# RP2040.net
KiCad netlist of a schematic drawn in Altium Designer
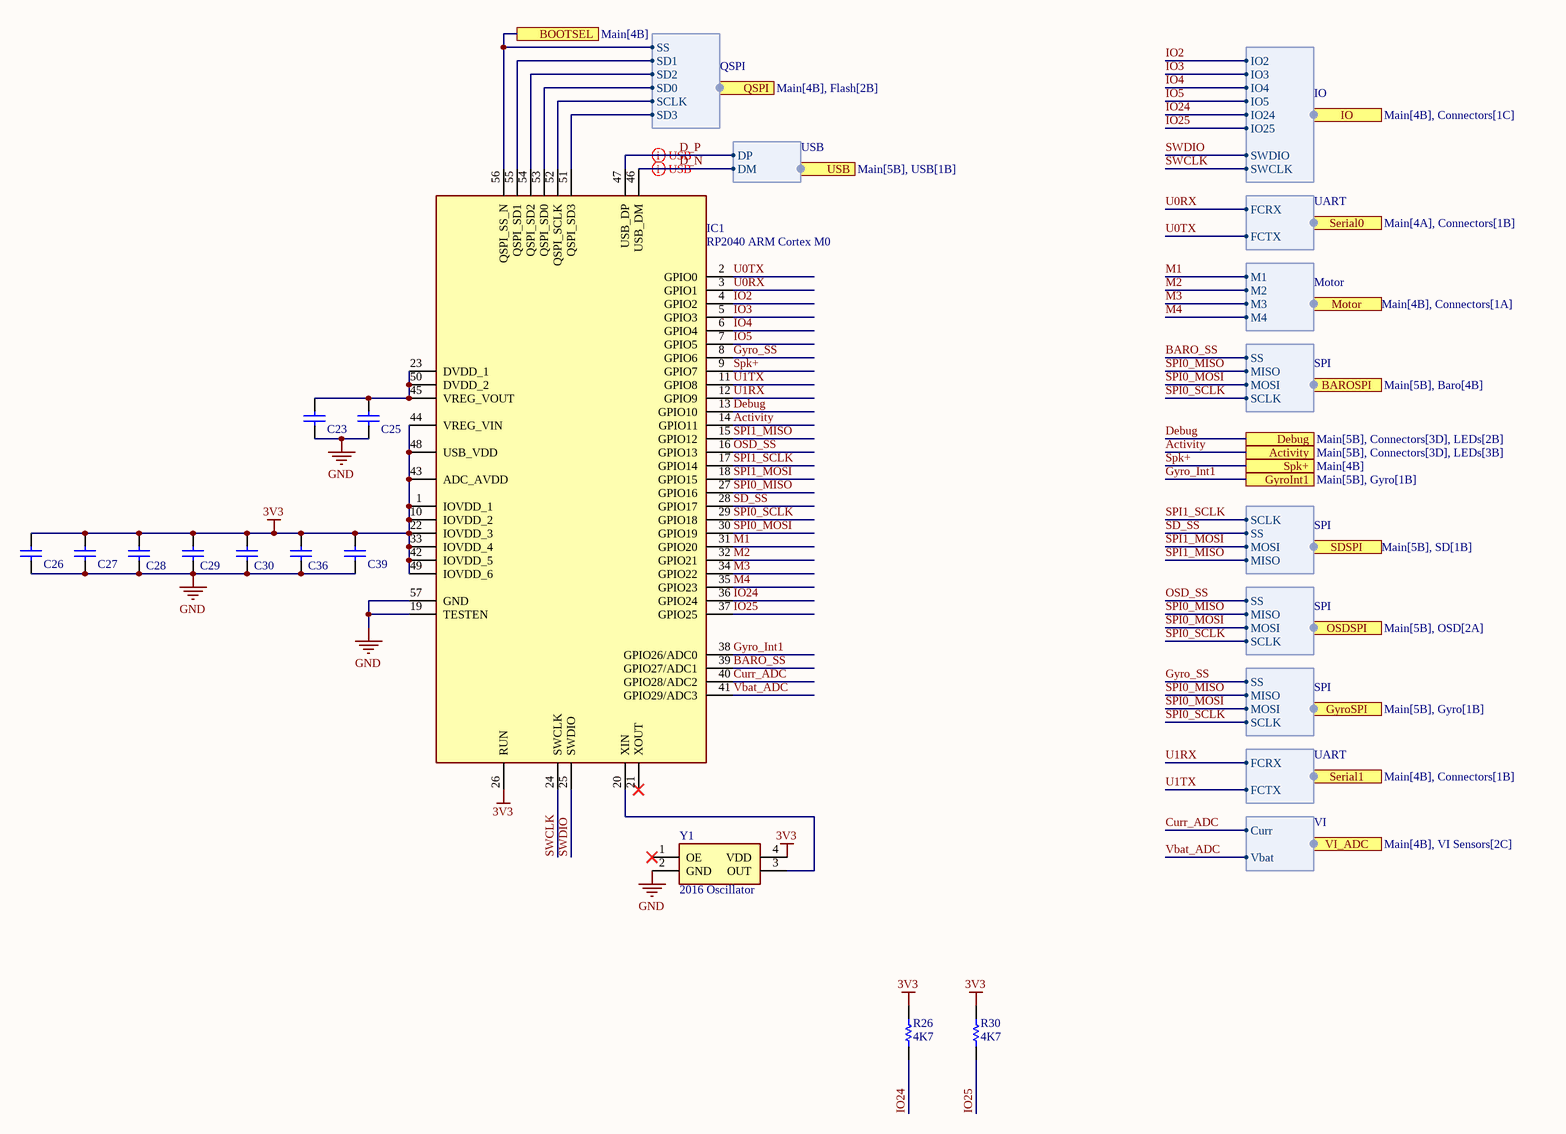
[diagram p0: RP2040.SchDoc]

(export (version "E")
  (design (tool "Eeschema 10.0.6"))
  (components
    (comp (ref "C23")
      (value "100nF")
      (footprint "WCAP-CSGP_0402_L1W0.5H0.5")
      (description "WCAP-CSGP Multilayer Ceramic Chip Capacitor, General Purpose, size 0402, X7R, 100nF, 50VDC")
      (fields
        (field (name "MANUFACTURER PART NUMBER") "885012205086")
        (field (name "MANUFACTURER") "Wurth Elektronik")
      )
      (libsource (lib "Altium_WCAP-CSGP (rev22f)") (part "885012205086"))
    )
    (comp (ref "C25")
      (value "100nF")
      (footprint "WCAP-CSGP_0402_L1W0.5H0.5")
      (description "WCAP-CSGP Multilayer Ceramic Chip Capacitor, General Purpose, size 0402, X7R, 100nF, 50VDC")
      (fields
        (field (name "MANUFACTURER PART NUMBER") "885012205086")
        (field (name "MANUFACTURER") "Wurth Elektronik")
      )
      (libsource (lib "Altium_WCAP-CSGP (rev22f)") (part "885012205086"))
    )
    (comp (ref "C26")
      (value "100nF")
      (footprint "WCAP-CSGP_0402_L1W0.5H0.5")
      (description "WCAP-CSGP Multilayer Ceramic Chip Capacitor, General Purpose, size 0402, X7R, 100nF, 50VDC")
      (fields
        (field (name "MANUFACTURER PART NUMBER") "885012205086")
        (field (name "MANUFACTURER") "Wurth Elektronik")
      )
      (libsource (lib "Altium_WCAP-CSGP (rev22f)") (part "885012205086"))
    )
    (comp (ref "C27")
      (value "100nF")
      (footprint "WCAP-CSGP_0402_L1W0.5H0.5")
      (description "WCAP-CSGP Multilayer Ceramic Chip Capacitor, General Purpose, size 0402, X7R, 100nF, 50VDC")
      (fields
        (field (name "MANUFACTURER PART NUMBER") "885012205086")
        (field (name "MANUFACTURER") "Wurth Elektronik")
      )
      (libsource (lib "Altium_WCAP-CSGP (rev22f)") (part "885012205086"))
    )
    (comp (ref "C28")
      (value "100nF")
      (footprint "WCAP-CSGP_0603_L1.6W0.8H0.8_Reflow")
      (description "WCAP-CSGP Multilayer Ceramic Chip Capacitor, General Purpose, size 0603, X7R, 100nF, 50VDC")
      (fields
        (field (name "MANUFACTURER PART NUMBER") "885012206095")
        (field (name "MANUFACTURER") "Wurth Elektronik")
      )
      (libsource (lib "Altium_WCAP-CSGP (rev22f)") (part "885012206095"))
    )
    (comp (ref "C29")
      (value "100nF")
      (footprint "WCAP-CSGP_0603_L1.6W0.8H0.8_Reflow")
      (description "WCAP-CSGP Multilayer Ceramic Chip Capacitor, General Purpose, size 0603, X7R, 100nF, 50VDC")
      (fields
        (field (name "MANUFACTURER PART NUMBER") "885012206095")
        (field (name "MANUFACTURER") "Wurth Elektronik")
      )
      (libsource (lib "Altium_WCAP-CSGP (rev22f)") (part "885012206095"))
    )
    (comp (ref "C30")
      (value "100nF")
      (footprint "WCAP-CSGP_0603_L1.6W0.8H0.8_Reflow")
      (description "WCAP-CSGP Multilayer Ceramic Chip Capacitor, General Purpose, size 0603, X7R, 100nF, 50VDC")
      (fields
        (field (name "MANUFACTURER PART NUMBER") "885012206095")
        (field (name "MANUFACTURER") "Wurth Elektronik")
      )
      (libsource (lib "Altium_WCAP-CSGP (rev22f)") (part "885012206095"))
    )
    (comp (ref "C36")
      (value "100nF")
      (footprint "WCAP-CSGP_0603_L1.6W0.8H0.8_Reflow")
      (description "WCAP-CSGP Multilayer Ceramic Chip Capacitor, General Purpose, size 0603, X7R, 100nF, 50VDC")
      (fields
        (field (name "MANUFACTURER PART NUMBER") "885012206095")
        (field (name "MANUFACTURER") "Wurth Elektronik")
      )
      (libsource (lib "Altium_WCAP-CSGP (rev22f)") (part "885012206095"))
    )
    (comp (ref "C39")
      (value "100nF")
      (footprint "WCAP-CSGP_0402_L1W0.5H0.5")
      (description "WCAP-CSGP Multilayer Ceramic Chip Capacitor, General Purpose, size 0402, X7R, 100nF, 50VDC")
      (fields
        (field (name "MANUFACTURER PART NUMBER") "885012205086")
        (field (name "MANUFACTURER") "Wurth Elektronik")
      )
      (libsource (lib "Altium_WCAP-CSGP (rev22f)") (part "885012205086"))
    )
    (comp (ref "IC1")
      (value "RP2040 ARM Cortex M0")
      (footprint "Custom Components:SC091413")
      (description "Microcontroller")
      (fields
        (field (name "MANUFACTURER_PART_NUMBER") "SC0914(13)")
        (field (name "MOUSER PART NUMBER") "358-SC091413")
      )
      (libsource (lib "Custom Components") (part "RP2040"))
    )
    (comp (ref "R26")
      (value "4K7")
      (footprint "RESC0603(1608)_N")
      (description "Chipwiderstand, SMD, Baureihe MC, 5%")
      (fields (field (name "MANUFACTURER") "Multicomp"))
      (libsource (lib "Standardbauteile") (part "Res 4k7"))
    )
    (comp (ref "R30")
      (value "4K7")
      (footprint "RESC0603(1608)_N")
      (description "Chipwiderstand, SMD, Baureihe MC, 5%")
      (fields (field (name "MANUFACTURER") "Multicomp"))
      (libsource (lib "Standardbauteile") (part "Res 4k7"))
    )
    (comp (ref "Y1")
      (value "2016 Oscillator")
      (footprint "Custom Components:2016 Oscillator")
      (description "YXC OT201612MJBA4SL")
      (fields
        (field (name "MANUFACTURER_PART_NUMBER") "DSC6003MA3B-032K768")
        (field (name "MOUSER PART NUMBER") "579-6003MA3B032K768")
      )
      (libsource (lib "Custom Components") (part "2016 Oscillator"))
    )
  )
  (nets
    (net (code "8") (name "/Activity") (class "Default")
      (node (ref "IC1") (pin "14") (pinfunction "GPIO11_14") (pintype "passive"))
    )
    (net (code "9") (name "/BARO_SS") (class "Default")
      (node (ref "IC1") (pin "39") (pinfunction "GPIO27/ADC1_39") (pintype "passive"))
    )
    (net (code "10") (name "/BOOTSEL") (class "Default")
      (node (ref "IC1") (pin "56") (pinfunction "QSPI_SS_N_56") (pintype "passive"))
    )
    (net (code "11") (name "/Curr_ADC") (class "Default")
      (node (ref "IC1") (pin "40") (pinfunction "GPIO28/ADC2_40") (pintype "passive"))
    )
    (net (code "12") (name "/D_N") (class "Default")
      (node (ref "IC1") (pin "46") (pinfunction "USB_DM_46") (pintype "passive"))
    )
    (net (code "13") (name "/D_P") (class "Default")
      (node (ref "IC1") (pin "47") (pinfunction "USB_DP_47") (pintype "passive"))
    )
    (net (code "14") (name "/Debug") (class "Default")
      (node (ref "IC1") (pin "13") (pinfunction "GPIO10_13") (pintype "passive"))
    )
    (net (code "15") (name "/Gyro_Int1") (class "Default")
      (node (ref "IC1") (pin "38") (pinfunction "GPIO26/ADC0_38") (pintype "passive"))
    )
    (net (code "16") (name "/Gyro_SS") (class "Default")
      (node (ref "IC1") (pin "8") (pinfunction "GPIO6_8") (pintype "passive"))
    )
    (net (code "17") (name "/IO2") (class "Default")
      (node (ref "IC1") (pin "4") (pinfunction "GPIO2_4") (pintype "passive"))
    )
    (net (code "18") (name "/IO3") (class "Default")
      (node (ref "IC1") (pin "5") (pinfunction "GPIO3_5") (pintype "passive"))
    )
    (net (code "19") (name "/IO4") (class "Default")
      (node (ref "IC1") (pin "6") (pinfunction "GPIO4_6") (pintype "passive"))
    )
    (net (code "20") (name "/IO5") (class "Default")
      (node (ref "IC1") (pin "7") (pinfunction "GPIO5_7") (pintype "passive"))
    )
    (net (code "21") (name "/IO24") (class "Default")
      (node (ref "IC1") (pin "36") (pinfunction "GPIO24_36") (pintype "passive"))
      (node (ref "R26") (pin "1") (pinfunction "1_1") (pintype "passive"))
    )
    (net (code "22") (name "/IO25") (class "Default")
      (node (ref "IC1") (pin "37") (pinfunction "GPIO25_37") (pintype "passive"))
      (node (ref "R30") (pin "1") (pinfunction "1_1") (pintype "passive"))
    )
    (net (code "23") (name "/M1") (class "Default")
      (node (ref "IC1") (pin "31") (pinfunction "GPIO20_31") (pintype "passive"))
    )
    (net (code "24") (name "/M2") (class "Default")
      (node (ref "IC1") (pin "32") (pinfunction "GPIO21_32") (pintype "passive"))
    )
    (net (code "25") (name "/M3") (class "Default")
      (node (ref "IC1") (pin "34") (pinfunction "GPIO22_34") (pintype "passive"))
    )
    (net (code "26") (name "/M4") (class "Default")
      (node (ref "IC1") (pin "35") (pinfunction "GPIO23_35") (pintype "passive"))
    )
    (net (code "27") (name "/OSD_SS") (class "Default")
      (node (ref "IC1") (pin "16") (pinfunction "GPIO13_16") (pintype "passive"))
    )
    (net (code "28") (name "/SD0") (class "Default")
      (node (ref "IC1") (pin "53") (pinfunction "QSPI_SD0_53") (pintype "passive"))
    )
    (net (code "29") (name "/SD1") (class "Default")
      (node (ref "IC1") (pin "55") (pinfunction "QSPI_SD1_55") (pintype "passive"))
    )
    (net (code "30") (name "/SD2") (class "Default")
      (node (ref "IC1") (pin "54") (pinfunction "QSPI_SD2_54") (pintype "passive"))
    )
    (net (code "31") (name "/SD3") (class "Default")
      (node (ref "IC1") (pin "51") (pinfunction "QSPI_SD3_51") (pintype "passive"))
    )
    (net (code "32") (name "/SD_SS") (class "Default")
      (node (ref "IC1") (pin "28") (pinfunction "GPIO17_28") (pintype "passive"))
    )
    (net (code "33") (name "/SPI0_MISO") (class "Default")
      (node (ref "IC1") (pin "27") (pinfunction "GPIO16_27") (pintype "passive"))
    )
    (net (code "34") (name "/SPI0_MOSI") (class "Default")
      (node (ref "IC1") (pin "30") (pinfunction "GPIO19_30") (pintype "passive"))
    )
    (net (code "35") (name "/SPI0_SCLK") (class "Default")
      (node (ref "IC1") (pin "29") (pinfunction "GPIO18_29") (pintype "passive"))
    )
    (net (code "36") (name "/SPI1_MISO") (class "Default")
      (node (ref "IC1") (pin "15") (pinfunction "GPIO12_15") (pintype "passive"))
    )
    (net (code "37") (name "/SPI1_MOSI") (class "Default")
      (node (ref "IC1") (pin "18") (pinfunction "GPIO15_18") (pintype "passive"))
    )
    (net (code "38") (name "/SPI1_SCLK") (class "Default")
      (node (ref "IC1") (pin "17") (pinfunction "GPIO14_17") (pintype "passive"))
    )
    (net (code "39") (name "/SWCLK") (class "Default")
      (node (ref "IC1") (pin "24") (pinfunction "SWCLK_24") (pintype "passive"))
    )
    (net (code "40") (name "/SWDIO") (class "Default")
      (node (ref "IC1") (pin "25") (pinfunction "SWDIO_25") (pintype "passive"))
    )
    (net (code "41") (name "/Spk+") (class "Default")
      (node (ref "IC1") (pin "9") (pinfunction "GPIO7_9") (pintype "passive"))
    )
    (net (code "42") (name "/U0RX") (class "Default")
      (node (ref "IC1") (pin "3") (pinfunction "GPIO1_3") (pintype "passive"))
    )
    (net (code "43") (name "/U0TX") (class "Default")
      (node (ref "IC1") (pin "2") (pinfunction "GPIO0_2") (pintype "passive"))
    )
    (net (code "44") (name "/U1RX") (class "Default")
      (node (ref "IC1") (pin "12") (pinfunction "GPIO9_12") (pintype "passive"))
    )
    (net (code "45") (name "/U1TX") (class "Default")
      (node (ref "IC1") (pin "11") (pinfunction "GPIO8_11") (pintype "passive"))
    )
    (net (code "46") (name "/Vbat_ADC") (class "Default")
      (node (ref "IC1") (pin "41") (pinfunction "GPIO29/ADC3_41") (pintype "passive"))
    )
    (net (code "54") (name "3V3") (class "Default")
      (node (ref "C26") (pin "2") (pinfunction "2_2") (pintype "passive"))
      (node (ref "C27") (pin "2") (pinfunction "2_2") (pintype "passive"))
      (node (ref "C28") (pin "2") (pinfunction "2_2") (pintype "passive"))
      (node (ref "C29") (pin "2") (pinfunction "2_2") (pintype "passive"))
      (node (ref "C30") (pin "2") (pinfunction "2_2") (pintype "passive"))
      (node (ref "C36") (pin "2") (pinfunction "2_2") (pintype "passive"))
      (node (ref "C39") (pin "2") (pinfunction "2_2") (pintype "passive"))
      (node (ref "IC1") (pin "1") (pinfunction "IOVDD_1_1") (pintype "passive"))
      (node (ref "IC1") (pin "10") (pinfunction "IOVDD_2_10") (pintype "passive"))
      (node (ref "IC1") (pin "22") (pinfunction "IOVDD_3_22") (pintype "passive"))
      (node (ref "IC1") (pin "26") (pinfunction "RUN_26") (pintype "passive"))
      (node (ref "IC1") (pin "33") (pinfunction "IOVDD_4_33") (pintype "passive"))
      (node (ref "IC1") (pin "42") (pinfunction "IOVDD_5_42") (pintype "passive"))
      (node (ref "IC1") (pin "43") (pinfunction "ADC_AVDD_43") (pintype "passive"))
      (node (ref "IC1") (pin "44") (pinfunction "VREG_VIN_44") (pintype "passive"))
      (node (ref "IC1") (pin "48") (pinfunction "USB_VDD_48") (pintype "passive"))
      (node (ref "IC1") (pin "49") (pinfunction "IOVDD_6_49") (pintype "passive"))
      (node (ref "R26") (pin "2") (pinfunction "2_2") (pintype "passive"))
      (node (ref "R30") (pin "2") (pinfunction "2_2") (pintype "passive"))
      (node (ref "Y1") (pin "4") (pinfunction "VDD_4") (pintype "passive"))
    )
    (net (code "55") (name "GND") (class "Default")
      (node (ref "C23") (pin "1") (pinfunction "1_1") (pintype "passive"))
      (node (ref "C25") (pin "1") (pinfunction "1_1") (pintype "passive"))
      (node (ref "C26") (pin "1") (pinfunction "1_1") (pintype "passive"))
      (node (ref "C27") (pin "1") (pinfunction "1_1") (pintype "passive"))
      (node (ref "C28") (pin "1") (pinfunction "1_1") (pintype "passive"))
      (node (ref "C29") (pin "1") (pinfunction "1_1") (pintype "passive"))
      (node (ref "C30") (pin "1") (pinfunction "1_1") (pintype "passive"))
      (node (ref "C36") (pin "1") (pinfunction "1_1") (pintype "passive"))
      (node (ref "C39") (pin "1") (pinfunction "1_1") (pintype "passive"))
      (node (ref "IC1") (pin "19") (pinfunction "TESTEN_19") (pintype "passive"))
      (node (ref "IC1") (pin "57") (pinfunction "GND_57") (pintype "passive"))
      (node (ref "Y1") (pin "2") (pinfunction "GND_2") (pintype "passive"))
    )
    (net (code "56") (name "Net-(IC1-DVDD_1)") (class "Default")
      (node (ref "C23") (pin "2") (pinfunction "2_2") (pintype "passive"))
      (node (ref "C25") (pin "2") (pinfunction "2_2") (pintype "passive"))
      (node (ref "IC1") (pin "23") (pinfunction "DVDD_1_23") (pintype "passive"))
      (node (ref "IC1") (pin "45") (pinfunction "VREG_VOUT_45") (pintype "passive"))
      (node (ref "IC1") (pin "50") (pinfunction "DVDD_2_50") (pintype "passive"))
    )
    (net (code "57") (name "Net-(IC1-XIN)") (class "Default")
      (node (ref "IC1") (pin "20") (pinfunction "XIN_20") (pintype "passive"))
      (node (ref "Y1") (pin "3") (pinfunction "OUT_3") (pintype "passive"))
    )
    (net (code "58") (name "unconnected-(IC1-QSPI_SCLK-Pad52)") (class "Default")
      (node (ref "IC1") (pin "52") (pinfunction "QSPI_SCLK_52") (pintype "passive"))
    )
    (net (code "59") (name "unconnected-(IC1-XOUT-Pad21)") (class "Default")
      (node (ref "IC1") (pin "21") (pinfunction "XOUT_21") (pintype "passive+no_connect"))
    )
    (net (code "60") (name "unconnected-(Y1-OE-Pad1)") (class "Default")
      (node (ref "Y1") (pin "1") (pinfunction "OE_1") (pintype "passive+no_connect"))
    )
  )
)
